# pic_board_with_lcd.net
KiCad netlist of a schematic drawn in EAGLE
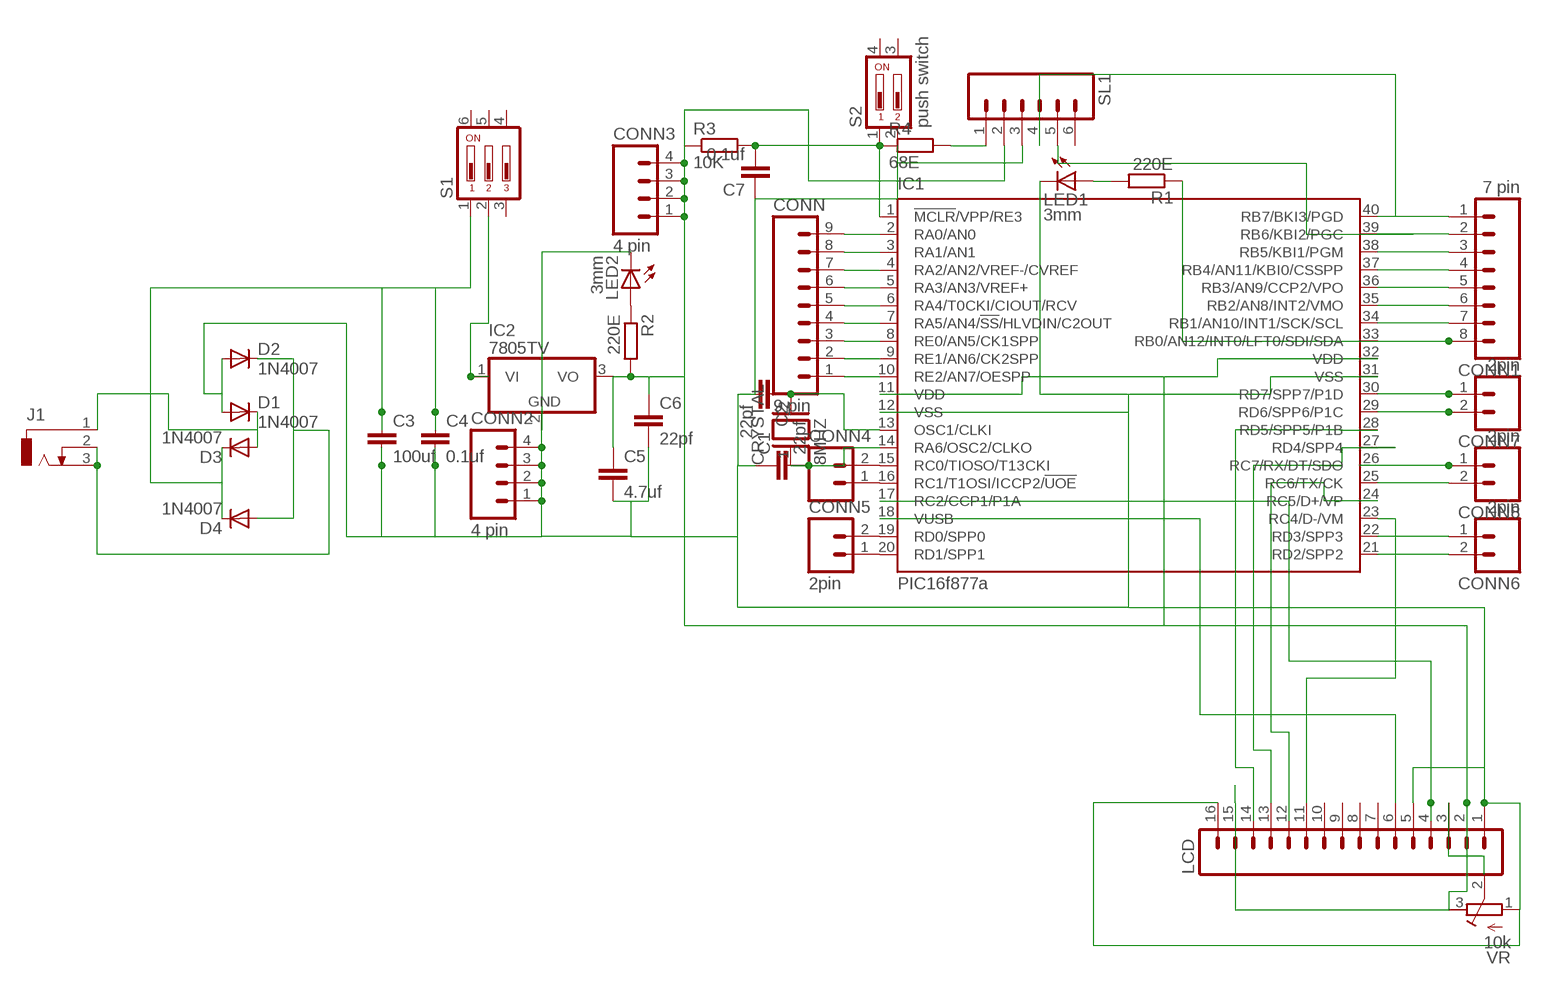
[diagram p0: schematic, sheet 1]

(export (version "E")
  (design (tool "Eeschema 10.0.6"))
  (components
    (comp (ref "C1")
      (value "22pf")
      (footprint "eagle-import:C2.5-2")
      (libsource (lib "eagle-import") (part "C2.5/2"))
    )
    (comp (ref "C2")
      (value "22pf")
      (footprint "eagle-import:C2.5-2")
      (libsource (lib "eagle-import") (part "C2.5/2"))
    )
    (comp (ref "C3")
      (value "100uf")
      (footprint "eagle-import:C5B7.2")
      (libsource (lib "eagle-import") (part "C5/7.2"))
    )
    (comp (ref "C4")
      (value "0.1uf")
      (footprint "eagle-import:C2.5-3")
      (libsource (lib "eagle-import") (part "C2,5-3"))
    )
    (comp (ref "C5")
      (value "4.7uf")
      (footprint "eagle-import:C5B7.2")
      (libsource (lib "eagle-import") (part "C5/7.2"))
    )
    (comp (ref "C6")
      (value "22pf")
      (footprint "eagle-import:C2.5-2")
      (libsource (lib "eagle-import") (part "C2.5/2"))
    )
    (comp (ref "C7")
      (value "0.1uf")
      (footprint "eagle-import:C2.5-3")
      (libsource (lib "eagle-import") (part "C2,5-3"))
    )
    (comp (ref "CONN")
      (value "9 pin")
      (footprint "eagle-import:09P")
      (libsource (lib "eagle-import") (part "M09"))
    )
    (comp (ref "CONN1")
      (value "7 pin")
      (footprint "eagle-import:08P")
      (libsource (lib "eagle-import") (part "M08"))
    )
    (comp (ref "CONN2")
      (value "4 pin")
      (footprint "eagle-import:04P")
      (libsource (lib "eagle-import") (part "M04"))
    )
    (comp (ref "CONN3")
      (value "4 pin")
      (footprint "eagle-import:04P")
      (libsource (lib "eagle-import") (part "M04"))
    )
    (comp (ref "CONN4")
      (value "M02")
      (footprint "eagle-import:02P")
      (libsource (lib "eagle-import") (part "M02"))
    )
    (comp (ref "CONN5")
      (value "2pin")
      (footprint "eagle-import:02P")
      (libsource (lib "eagle-import") (part "M02"))
    )
    (comp (ref "CONN6")
      (value "2pin")
      (footprint "eagle-import:02P")
      (libsource (lib "eagle-import") (part "M02"))
    )
    (comp (ref "CONN7")
      (value "2pin")
      (footprint "eagle-import:02P")
      (fields (field (name "OC_FARNELL") "unknown") (field (name "OC_NEWARK") "unknown"))
      (libsource (lib "eagle-import") (part "M02"))
    )
    (comp (ref "CONN8")
      (value "2pin")
      (footprint "eagle-import:02P")
      (fields (field (name "OC_FARNELL") "unknown") (field (name "OC_NEWARK") "unknown"))
      (libsource (lib "eagle-import") (part "M02"))
    )
    (comp (ref "CRYSTAL")
      (value "8MHZ")
      (footprint "eagle-import:QS")
      (libsource (lib "eagle-import") (part "XTAL/S"))
    )
    (comp (ref "D1")
      (value "1N4007")
      (footprint "eagle-import:DO41-10")
      (libsource (lib "eagle-import") (part "1N4004"))
    )
    (comp (ref "D2")
      (value "1N4007")
      (footprint "eagle-import:DO41-10")
      (libsource (lib "eagle-import") (part "1N4004"))
    )
    (comp (ref "D3")
      (value "1N4007")
      (footprint "eagle-import:DO41-10")
      (libsource (lib "eagle-import") (part "1N4004"))
    )
    (comp (ref "D4")
      (value "1N4007")
      (footprint "eagle-import:DO41-10")
      (libsource (lib "eagle-import") (part "1N4004"))
    )
    (comp (ref "IC1")
      (value "PIC16f877a")
      (footprint "eagle-import:DIL40")
      (fields (field (name "MF") "MICROCHIP") (field (name "MPN") "PIC18F4455-I/P"))
      (libsource (lib "eagle-import") (part "PIC18F4_40455"))
    )
    (comp (ref "IC2")
      (value "7805TV")
      (footprint "eagle-import:TO220V")
      (libsource (lib "eagle-import") (part "78TV05"))
    )
    (comp (ref "J1")
      (value "DCJ0303")
      (footprint "eagle-import:DCJ0303")
      (libsource (lib "eagle-import") (part "DCJ0303"))
    )
    (comp (ref "LCD")
      (value "M16")
      (footprint "eagle-import:16P")
      (libsource (lib "eagle-import") (part "M16"))
    )
    (comp (ref "LED1")
      (value "3mm")
      (footprint "eagle-import:LED3MM")
      (libsource (lib "eagle-import") (part "LED3MM"))
    )
    (comp (ref "LED2")
      (value "3mm")
      (footprint "eagle-import:LED3MM")
      (libsource (lib "eagle-import") (part "LED3MM"))
    )
    (comp (ref "R1")
      (value "220E")
      (footprint "eagle-import:0204_7")
      (libsource (lib "eagle-import") (part "R-EU_0204/7"))
    )
    (comp (ref "R2")
      (value "220E")
      (footprint "eagle-import:0204_7")
      (libsource (lib "eagle-import") (part "R-EU_0204/7"))
    )
    (comp (ref "R3")
      (value "10K")
      (footprint "eagle-import:0204_7")
      (libsource (lib "eagle-import") (part "R-EU_0204/7"))
    )
    (comp (ref "R4")
      (value "68E")
      (footprint "eagle-import:0204_7")
      (libsource (lib "eagle-import") (part "R-EU_0204/7"))
    )
    (comp (ref "S1")
      (value "DA03")
      (footprint "eagle-import:DA-03")
      (fields (field (name "MPN") "MCDA03"))
      (libsource (lib "eagle-import") (part "DA03"))
    )
    (comp (ref "S2")
      (value "push switch")
      (footprint "eagle-import:DP-02")
      (fields (field (name "MPN") "MCDP02"))
      (libsource (lib "eagle-import") (part "DP02"))
    )
    (comp (ref "SL1")
      (value "M06")
      (footprint "eagle-import:06P")
      (libsource (lib "eagle-import") (part "M06"))
    )
    (comp (ref "VR")
      (value "10k")
      (footprint "eagle-import:RTRIM64P")
      (libsource (lib "eagle-import") (part "R-TRIMM64P"))
    )
  )
  (nets
    (net (code "1") (name "Net-(C3-Pad1)") (class "Default")
      (node (ref "C3") (pin "1") (pinfunction "1_1") (pintype "passive"))
      (node (ref "C4") (pin "1") (pinfunction "1_1") (pintype "passive"))
      (node (ref "D3") (pin "C") (pinfunction "C_C") (pintype "passive"))
      (node (ref "D4") (pin "C") (pinfunction "C_C") (pintype "passive"))
      (node (ref "S1") (pin "1") (pinfunction "1_1") (pintype "passive"))
    )
    (net (code "2") (name "Net-(D1-PadC)") (class "Default")
      (node (ref "D1") (pin "C") (pinfunction "C_C") (pintype "passive"))
      (node (ref "D3") (pin "A") (pinfunction "A_A") (pintype "passive"))
      (node (ref "J1") (pin "1") (pinfunction "1_1") (pintype "passive"))
    )
    (net (code "3") (name "Net-(D2-PadC)") (class "Default")
      (node (ref "D2") (pin "C") (pinfunction "C_C") (pintype "passive"))
      (node (ref "D4") (pin "A") (pinfunction "A_A") (pintype "passive"))
      (node (ref "J1") (pin "2") (pinfunction "2_2") (pintype "passive"))
      (node (ref "J1") (pin "3") (pinfunction "3_3") (pintype "passive"))
    )
    (net (code "4") (name "Net-(IC1-OSC1{slash}CLKI)") (class "Default")
      (node (ref "C2") (pin "1") (pinfunction "1_1") (pintype "passive"))
      (node (ref "CRYSTAL") (pin "2") (pinfunction "2_2") (pintype "passive"))
      (node (ref "IC1") (pin "13") (pinfunction "OSC1/CLKI_13") (pintype "input"))
    )
    (net (code "5") (name "Net-(IC1-RA0{slash}AN0)") (class "Default")
      (node (ref "CONN") (pin "9") (pinfunction "9_9") (pintype "passive"))
      (node (ref "IC1") (pin "2") (pinfunction "RA0/AN0_2") (pintype "bidirectional"))
    )
    (net (code "6") (name "Net-(IC1-RA1{slash}AN1)") (class "Default")
      (node (ref "CONN") (pin "8") (pinfunction "8_8") (pintype "passive"))
      (node (ref "IC1") (pin "3") (pinfunction "RA1/AN1_3") (pintype "bidirectional"))
    )
    (net (code "7") (name "Net-(IC1-RA2{slash}AN2{slash}VREF-{slash}CVREF)") (class "Default")
      (node (ref "CONN") (pin "7") (pinfunction "7_7") (pintype "passive"))
      (node (ref "IC1") (pin "4") (pinfunction "RA2/AN2/VREF-/CVREF_4") (pintype "bidirectional"))
    )
    (net (code "8") (name "Net-(IC1-RA3{slash}AN3{slash}VREF+)") (class "Default")
      (node (ref "CONN") (pin "6") (pinfunction "6_6") (pintype "passive"))
      (node (ref "IC1") (pin "5") (pinfunction "RA3/AN3/VREF+_5") (pintype "bidirectional"))
    )
    (net (code "9") (name "Net-(IC1-RA4{slash}T0CKI{slash}CIOUT{slash}RCV)") (class "Default")
      (node (ref "CONN") (pin "5") (pinfunction "5_5") (pintype "passive"))
      (node (ref "IC1") (pin "6") (pinfunction "RA4/T0CKI/CIOUT/RCV_6") (pintype "bidirectional"))
    )
    (net (code "10") (name "Net-(IC1-RA5{slash}AN4{slash}~{SS}{slash}HLVDIN{slash}C2OUT)") (class "Default")
      (node (ref "CONN") (pin "4") (pinfunction "4_4") (pintype "passive"))
      (node (ref "IC1") (pin "7") (pinfunction "RA5/AN4/~{SS}/HLVDIN/C2OUT_7") (pintype "bidirectional"))
    )
    (net (code "11") (name "Net-(IC1-RA6{slash}OSC2{slash}CLKO)") (class "Default")
      (node (ref "C1") (pin "2") (pinfunction "2_2") (pintype "passive"))
      (node (ref "CRYSTAL") (pin "1") (pinfunction "1_1") (pintype "passive"))
      (node (ref "IC1") (pin "14") (pinfunction "RA6/OSC2/CLKO_14") (pintype "output"))
    )
    (net (code "12") (name "Net-(IC1-RB0{slash}AN12{slash}INT0{slash}LFT0{slash}SDI{slash}SDA)") (class "Default")
      (node (ref "CONN1") (pin "8") (pinfunction "8_8") (pintype "passive"))
      (node (ref "IC1") (pin "33") (pinfunction "RB0/AN12/INT0/LFT0/SDI/SDA_33") (pintype "bidirectional"))
      (node (ref "R1") (pin "1") (pinfunction "1_1") (pintype "passive"))
    )
    (net (code "13") (name "Net-(IC1-RB1{slash}AN10{slash}INT1{slash}SCK{slash}SCL)") (class "Default")
      (node (ref "CONN1") (pin "7") (pinfunction "7_7") (pintype "passive"))
      (node (ref "IC1") (pin "34") (pinfunction "RB1/AN10/INT1/SCK/SCL_34") (pintype "bidirectional"))
    )
    (net (code "14") (name "Net-(IC1-RB2{slash}AN8{slash}INT2{slash}VMO)") (class "Default")
      (node (ref "CONN1") (pin "6") (pinfunction "6_6") (pintype "passive"))
      (node (ref "IC1") (pin "35") (pinfunction "RB2/AN8/INT2/VMO_35") (pintype "bidirectional"))
    )
    (net (code "15") (name "Net-(IC1-RB3{slash}AN9{slash}CCP2{slash}VPO)") (class "Default")
      (node (ref "CONN1") (pin "5") (pinfunction "5_5") (pintype "passive"))
      (node (ref "IC1") (pin "36") (pinfunction "RB3/AN9/CCP2/VPO_36") (pintype "bidirectional"))
    )
    (net (code "16") (name "Net-(IC1-RB4{slash}AN11{slash}KBI0{slash}CSSPP)") (class "Default")
      (node (ref "CONN1") (pin "4") (pinfunction "4_4") (pintype "passive"))
      (node (ref "IC1") (pin "37") (pinfunction "RB4/AN11/KBI0/CSSPP_37") (pintype "bidirectional"))
    )
    (net (code "17") (name "Net-(IC1-RB5{slash}KBI1{slash}PGM)") (class "Default")
      (node (ref "CONN1") (pin "3") (pinfunction "3_3") (pintype "passive"))
      (node (ref "IC1") (pin "38") (pinfunction "RB5/KBI1/PGM_38") (pintype "bidirectional"))
    )
    (net (code "18") (name "Net-(IC1-RB6{slash}KBI2{slash}PGC)") (class "Default")
      (node (ref "CONN1") (pin "2") (pinfunction "2_2") (pintype "passive"))
      (node (ref "IC1") (pin "39") (pinfunction "RB6/KBI2/PGC_39") (pintype "bidirectional"))
      (node (ref "SL1") (pin "5") (pinfunction "5_5") (pintype "passive"))
    )
    (net (code "19") (name "Net-(IC1-RB7{slash}BKI3{slash}PGD)") (class "Default")
      (node (ref "CONN1") (pin "1") (pinfunction "1_1") (pintype "passive"))
      (node (ref "IC1") (pin "40") (pinfunction "RB7/BKI3/PGD_40") (pintype "bidirectional"))
      (node (ref "SL1") (pin "4") (pinfunction "4_4") (pintype "passive"))
    )
    (net (code "20") (name "Net-(IC1-RC0{slash}TIOSO{slash}T13CKI)") (class "Default")
      (node (ref "CONN4") (pin "2") (pinfunction "2_2") (pintype "passive"))
      (node (ref "IC1") (pin "15") (pinfunction "RC0/TIOSO/T13CKI_15") (pintype "bidirectional"))
    )
    (net (code "21") (name "Net-(IC1-RC1{slash}T1OSI{slash}ICCP2{slash}~{UOE})") (class "Default")
      (node (ref "CONN4") (pin "1") (pinfunction "1_1") (pintype "passive"))
      (node (ref "IC1") (pin "16") (pinfunction "RC1/T1OSI/ICCP2/~{UOE}_16") (pintype "bidirectional"))
    )
    (net (code "22") (name "Net-(IC1-RC2{slash}CCP1{slash}P1A)") (class "Default")
      (node (ref "IC1") (pin "17") (pinfunction "RC2/CCP1/P1A_17") (pintype "bidirectional"))
      (node (ref "LCD") (pin "4") (pinfunction "4_4") (pintype "passive"))
    )
    (net (code "23") (name "Net-(IC1-RC4{slash}D-{slash}VM)") (class "Default")
      (node (ref "IC1") (pin "23") (pinfunction "RC4/D-/VM_23") (pintype "bidirectional"))
      (node (ref "LCD") (pin "11") (pinfunction "11_11") (pintype "passive"))
    )
    (net (code "24") (name "Net-(IC1-RC5{slash}D+{slash}VP)") (class "Default")
      (node (ref "IC1") (pin "24") (pinfunction "RC5/D+/VP_24") (pintype "bidirectional"))
      (node (ref "LCD") (pin "12") (pinfunction "12_12") (pintype "passive"))
    )
    (net (code "25") (name "Net-(IC1-RC6{slash}TX{slash}CK)") (class "Default")
      (node (ref "CONN8") (pin "2") (pinfunction "2_2") (pintype "passive"))
      (node (ref "IC1") (pin "25") (pinfunction "RC6/TX/CK_25") (pintype "bidirectional"))
    )
    (net (code "26") (name "Net-(IC1-RC7{slash}RX{slash}DT{slash}SDO)") (class "Default")
      (node (ref "CONN8") (pin "1") (pinfunction "1_1") (pintype "passive"))
      (node (ref "IC1") (pin "26") (pinfunction "RC7/RX/DT/SDO_26") (pintype "bidirectional"))
    )
    (net (code "27") (name "Net-(IC1-RD0{slash}SPP0)") (class "Default")
      (node (ref "CONN5") (pin "2") (pinfunction "2_2") (pintype "passive"))
      (node (ref "IC1") (pin "19") (pinfunction "RD0/SPP0_19") (pintype "bidirectional"))
    )
    (net (code "28") (name "Net-(IC1-RD1{slash}SPP1)") (class "Default")
      (node (ref "CONN5") (pin "1") (pinfunction "1_1") (pintype "passive"))
      (node (ref "IC1") (pin "20") (pinfunction "RD1/SPP1_20") (pintype "bidirectional"))
    )
    (net (code "29") (name "Net-(IC1-RD2{slash}SPP2)") (class "Default")
      (node (ref "CONN6") (pin "2") (pinfunction "2_2") (pintype "passive"))
      (node (ref "IC1") (pin "21") (pinfunction "RD2/SPP2_21") (pintype "bidirectional"))
    )
    (net (code "30") (name "Net-(IC1-RD3{slash}SPP3)") (class "Default")
      (node (ref "CONN6") (pin "1") (pinfunction "1_1") (pintype "passive"))
      (node (ref "IC1") (pin "22") (pinfunction "RD3/SPP3_22") (pintype "bidirectional"))
    )
    (net (code "31") (name "Net-(IC1-RD4{slash}SPP4)") (class "Default")
      (node (ref "IC1") (pin "27") (pinfunction "RD4/SPP4_27") (pintype "bidirectional"))
      (node (ref "LCD") (pin "13") (pinfunction "13_13") (pintype "passive"))
    )
    (net (code "32") (name "Net-(IC1-RD5{slash}SPP5{slash}P1B)") (class "Default")
      (node (ref "IC1") (pin "28") (pinfunction "RD5/SPP5/P1B_28") (pintype "bidirectional"))
      (node (ref "LCD") (pin "14") (pinfunction "14_14") (pintype "passive"))
    )
    (net (code "33") (name "Net-(IC1-RD6{slash}SPP6{slash}P1C)") (class "Default")
      (node (ref "CONN7") (pin "2") (pinfunction "2_2") (pintype "passive"))
      (node (ref "IC1") (pin "29") (pinfunction "RD6/SPP6/P1C_29") (pintype "bidirectional"))
    )
    (net (code "34") (name "Net-(IC1-RD7{slash}SPP7{slash}P1D)") (class "Default")
      (node (ref "CONN7") (pin "1") (pinfunction "1_1") (pintype "passive"))
      (node (ref "IC1") (pin "30") (pinfunction "RD7/SPP7/P1D_30") (pintype "bidirectional"))
    )
    (net (code "35") (name "Net-(IC1-RE0{slash}AN5{slash}CK1SPP)") (class "Default")
      (node (ref "CONN") (pin "3") (pinfunction "3_3") (pintype "passive"))
      (node (ref "IC1") (pin "8") (pinfunction "RE0/AN5/CK1SPP_8") (pintype "bidirectional"))
    )
    (net (code "36") (name "Net-(IC1-RE1{slash}AN6{slash}CK2SPP)") (class "Default")
      (node (ref "CONN") (pin "2") (pinfunction "2_2") (pintype "passive"))
      (node (ref "IC1") (pin "9") (pinfunction "RE1/AN6/CK2SPP_9") (pintype "bidirectional"))
    )
    (net (code "37") (name "Net-(IC1-RE2{slash}AN7{slash}OESPP)") (class "Default")
      (node (ref "CONN") (pin "1") (pinfunction "1_1") (pintype "passive"))
      (node (ref "IC1") (pin "10") (pinfunction "RE2/AN7/OESPP_10") (pintype "bidirectional"))
    )
    (net (code "38") (name "Net-(IC1-VUSB)") (class "Default")
      (node (ref "IC1") (pin "18") (pinfunction "VUSB_18") (pintype "bidirectional"))
      (node (ref "LCD") (pin "6") (pinfunction "6_6") (pintype "passive"))
    )
    (net (code "39") (name "Net-(IC1-~{MCLR}{slash}VPP{slash}RE3)") (class "Default")
      (node (ref "C7") (pin "2") (pinfunction "2_2") (pintype "passive"))
      (node (ref "IC1") (pin "1") (pinfunction "~{MCLR}/VPP/RE3_1") (pintype "input"))
      (node (ref "R3") (pin "2") (pinfunction "2_2") (pintype "passive"))
      (node (ref "R4") (pin "1") (pinfunction "1_1") (pintype "passive"))
      (node (ref "S2") (pin "1") (pinfunction "1_1") (pintype "passive"))
    )
    (net (code "40") (name "Net-(IC2-GND)") (class "Default")
      (node (ref "C1") (pin "1") (pinfunction "1_1") (pintype "passive"))
      (node (ref "C2") (pin "2") (pinfunction "2_2") (pintype "passive"))
      (node (ref "C3") (pin "2") (pinfunction "2_2") (pintype "passive"))
      (node (ref "C4") (pin "2") (pinfunction "2_2") (pintype "passive"))
      (node (ref "C5") (pin "2") (pinfunction "2_2") (pintype "passive"))
      (node (ref "C6") (pin "2") (pinfunction "2_2") (pintype "passive"))
      (node (ref "C7") (pin "1") (pinfunction "1_1") (pintype "passive"))
      (node (ref "CONN2") (pin "1") (pinfunction "1_1") (pintype "passive"))
      (node (ref "CONN2") (pin "2") (pinfunction "2_2") (pintype "passive"))
      (node (ref "CONN2") (pin "3") (pinfunction "3_3") (pintype "passive"))
      (node (ref "CONN2") (pin "4") (pinfunction "4_4") (pintype "passive"))
      (node (ref "D1") (pin "A") (pinfunction "A_A") (pintype "passive"))
      (node (ref "D2") (pin "A") (pinfunction "A_A") (pintype "passive"))
      (node (ref "IC1") (pin "12") (pinfunction "VSS_12") (pintype "power_in"))
      (node (ref "IC1") (pin "31") (pinfunction "VSS_31") (pintype "power_in"))
      (node (ref "IC2") (pin "2") (pinfunction "GND_2") (pintype "passive"))
      (node (ref "LCD") (pin "1") (pinfunction "1_1") (pintype "passive"))
      (node (ref "LCD") (pin "16") (pinfunction "16_16") (pintype "passive"))
      (node (ref "LCD") (pin "5") (pinfunction "5_5") (pintype "passive"))
      (node (ref "LED1") (pin "K") (pinfunction "C_K") (pintype "passive"))
      (node (ref "LED2") (pin "K") (pinfunction "C_K") (pintype "passive"))
      (node (ref "S2") (pin "2") (pinfunction "2_2") (pintype "passive"))
      (node (ref "SL1") (pin "3") (pinfunction "3_3") (pintype "passive"))
      (node (ref "VR") (pin "1") (pinfunction "E_1") (pintype "passive"))
    )
    (net (code "41") (name "Net-(IC2-VI)") (class "Default")
      (node (ref "IC2") (pin "1") (pinfunction "VI_1") (pintype "input"))
      (node (ref "S1") (pin "2") (pinfunction "2_2") (pintype "passive"))
    )
    (net (code "42") (name "Net-(IC2-VO)") (class "Default")
      (node (ref "C5") (pin "1") (pinfunction "1_1") (pintype "passive"))
      (node (ref "C6") (pin "1") (pinfunction "1_1") (pintype "passive"))
      (node (ref "CONN3") (pin "1") (pinfunction "1_1") (pintype "passive"))
      (node (ref "CONN3") (pin "2") (pinfunction "2_2") (pintype "passive"))
      (node (ref "CONN3") (pin "3") (pinfunction "3_3") (pintype "passive"))
      (node (ref "CONN3") (pin "4") (pinfunction "4_4") (pintype "passive"))
      (node (ref "IC1") (pin "11") (pinfunction "VDD_11") (pintype "power_in"))
      (node (ref "IC1") (pin "32") (pinfunction "VDD_32") (pintype "power_in"))
      (node (ref "IC2") (pin "3") (pinfunction "VO_3") (pintype "passive"))
      (node (ref "LCD") (pin "15") (pinfunction "15_15") (pintype "passive"))
      (node (ref "LCD") (pin "2") (pinfunction "2_2") (pintype "passive"))
      (node (ref "R2") (pin "2") (pinfunction "2_2") (pintype "passive"))
      (node (ref "R3") (pin "1") (pinfunction "1_1") (pintype "passive"))
      (node (ref "SL1") (pin "2") (pinfunction "2_2") (pintype "passive"))
      (node (ref "VR") (pin "3") (pinfunction "A_3") (pintype "passive"))
    )
    (net (code "43") (name "Net-(LED1-PadA)") (class "Default")
      (node (ref "LED1") (pin "A") (pinfunction "A_A") (pintype "passive"))
      (node (ref "R1") (pin "2") (pinfunction "2_2") (pintype "passive"))
    )
    (net (code "44") (name "Net-(LED2-PadA)") (class "Default")
      (node (ref "LED2") (pin "A") (pinfunction "A_A") (pintype "passive"))
      (node (ref "R2") (pin "1") (pinfunction "1_1") (pintype "passive"))
    )
    (net (code "45") (name "Net-(R4-Pad2)") (class "Default")
      (node (ref "R4") (pin "2") (pinfunction "2_2") (pintype "passive"))
      (node (ref "SL1") (pin "1") (pinfunction "1_1") (pintype "passive"))
    )
    (net (code "46") (name "Net-(VR-S)") (class "Default")
      (node (ref "LCD") (pin "3") (pinfunction "3_3") (pintype "passive"))
      (node (ref "VR") (pin "2") (pinfunction "S_2") (pintype "passive"))
    )
    (net (code "47") (name "unconnected-(LCD-Pad7)") (class "Default")
      (node (ref "LCD") (pin "7") (pinfunction "7_7") (pintype "passive"))
    )
    (net (code "48") (name "unconnected-(LCD-Pad8)") (class "Default")
      (node (ref "LCD") (pin "8") (pinfunction "8_8") (pintype "passive"))
    )
    (net (code "49") (name "unconnected-(LCD-Pad9)") (class "Default")
      (node (ref "LCD") (pin "9") (pinfunction "9_9") (pintype "passive"))
    )
    (net (code "50") (name "unconnected-(LCD-Pad10)") (class "Default")
      (node (ref "LCD") (pin "10") (pinfunction "10_10") (pintype "passive"))
    )
    (net (code "51") (name "unconnected-(S1-Pad3)") (class "Default")
      (node (ref "S1") (pin "3") (pinfunction "3_3") (pintype "passive"))
    )
    (net (code "52") (name "unconnected-(S1-Pad4)") (class "Default")
      (node (ref "S1") (pin "4") (pinfunction "4_4") (pintype "passive"))
    )
    (net (code "53") (name "unconnected-(S1-Pad5)") (class "Default")
      (node (ref "S1") (pin "5") (pinfunction "5_5") (pintype "passive"))
    )
    (net (code "54") (name "unconnected-(S1-Pad6)") (class "Default")
      (node (ref "S1") (pin "6") (pinfunction "6_6") (pintype "passive"))
    )
    (net (code "55") (name "unconnected-(S2-Pad3)") (class "Default")
      (node (ref "S2") (pin "3") (pinfunction "3_3") (pintype "passive"))
    )
    (net (code "56") (name "unconnected-(S2-Pad4)") (class "Default")
      (node (ref "S2") (pin "4") (pinfunction "4_4") (pintype "passive"))
    )
    (net (code "57") (name "unconnected-(SL1-Pad6)") (class "Default")
      (node (ref "SL1") (pin "6") (pinfunction "6_6") (pintype "passive"))
    )
  )
)
